# 03_RADIO.net
KiCad netlist of a schematic drawn in Altium Designer
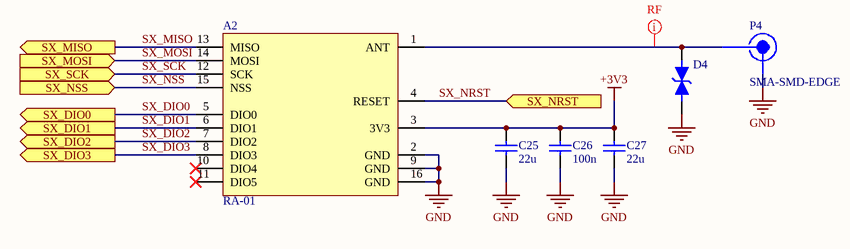
[diagram p0: 03_RADIO.SchDoc]

(export (version "E")
  (design (tool "Eeschema 10.0.6"))
  (components
    (comp (ref "A2")
      (value "RA-01")
      (footprint "RA-01")
      (description "Wireless Modules SX1278")
      (fields (field (name "MANUFACTURER") "Ai-Thinker"))
      (libsource (lib "alfasat_lib") (part "RA-01"))
    )
    (comp (ref "C25")
      (value "22u")
      (footprint "C0805_IPC_HD")
      (description "CAP CER 22UF 16V X5R 0805")
      (fields
        (field (name "MANUFACTURER") "Samsung Electro-Mechanics")
        (field (name "MANUFACTURER PART NUMBER") "CL21A226MOCLRNC")
      )
      (libsource (lib "alfasat_lib") (part "CL21A226MOCLRNC"))
    )
    (comp (ref "C26")
      (value "100n")
      (footprint "C0603_IPC_MD")
      (description "CAP CER 0.1UF 16V X7R 0603")
      (fields
        (field (name "MANUFACTURER") "Samsung Electro-Mechanics")
        (field (name "MANUFACTURER PART NUMBER") "CL10B104KO8NNNC")
      )
      (libsource (lib "alfasat_lib") (part "CL10B104KO8NNNC"))
    )
    (comp (ref "C27")
      (value "22u")
      (footprint "C0805_IPC_HD")
      (description "CAP CER 22UF 16V X5R 0805")
      (fields
        (field (name "MANUFACTURER") "Samsung Electro-Mechanics")
        (field (name "MANUFACTURER PART NUMBER") "CL21A226MOCLRNC")
      )
      (libsource (lib "alfasat_lib") (part "CL21A226MOCLRNC"))
    )
    (comp (ref "D4")
      (value "LXES15AAA1-153")
      (footprint "C0402_IPC_MD")
      (description "TVS DIODE 4V 0402")
      (fields (field (name "MANUFACTURER") "Murata Electronics North America"))
      (libsource (lib "alfasat_lib") (part "LXES15AAA1-153"))
    )
    (comp (ref "P4")
      (value "SMA-SMD-EDGE")
      (footprint "SMA-SMD-EDGE")
      (description "SMA SMD EDGE CONNECTER")
      (fields (field (name "MANUFACTURER") "China"))
      (libsource (lib "alfasat_lib") (part "SMA-SMD-EDGE"))
    )
  )
  (nets
    (net (code "1") (name "+3V3") (class "Default")
      (node (ref "A2") (pin "3") (pinfunction "3V3_3") (pintype "passive"))
      (node (ref "C25") (pin "1") (pinfunction "1_1") (pintype "passive"))
      (node (ref "C26") (pin "1") (pinfunction "1_1") (pintype "passive"))
      (node (ref "C27") (pin "1") (pinfunction "1_1") (pintype "passive"))
    )
    (net (code "2") (name "/SX_DIO0") (class "Default")
      (node (ref "A2") (pin "5") (pinfunction "DIO0_5") (pintype "passive"))
    )
    (net (code "3") (name "/SX_DIO1") (class "Default")
      (node (ref "A2") (pin "6") (pinfunction "DIO1_6") (pintype "passive"))
    )
    (net (code "4") (name "/SX_DIO2") (class "Default")
      (node (ref "A2") (pin "7") (pinfunction "DIO2_7") (pintype "passive"))
    )
    (net (code "5") (name "/SX_DIO3") (class "Default")
      (node (ref "A2") (pin "8") (pinfunction "DIO3_8") (pintype "passive"))
    )
    (net (code "6") (name "/SX_MISO") (class "Default")
      (node (ref "A2") (pin "13") (pinfunction "MISO_13") (pintype "passive"))
    )
    (net (code "7") (name "/SX_MOSI") (class "Default")
      (node (ref "A2") (pin "14") (pinfunction "MOSI_14") (pintype "passive"))
    )
    (net (code "8") (name "/SX_NRST") (class "Default")
      (node (ref "A2") (pin "4") (pinfunction "RESET_4") (pintype "passive"))
    )
    (net (code "9") (name "/SX_NSS") (class "Default")
      (node (ref "A2") (pin "15") (pinfunction "NSS_15") (pintype "passive"))
    )
    (net (code "10") (name "/SX_SCK") (class "Default")
      (node (ref "A2") (pin "12") (pinfunction "SCK_12") (pintype "passive"))
    )
    (net (code "11") (name "GND") (class "Default")
      (node (ref "A2") (pin "16") (pinfunction "GND_16") (pintype "passive"))
      (node (ref "A2") (pin "2") (pinfunction "GND_2") (pintype "passive"))
      (node (ref "A2") (pin "9") (pinfunction "GND_9") (pintype "passive"))
      (node (ref "C25") (pin "2") (pinfunction "2_2") (pintype "passive"))
      (node (ref "C26") (pin "2") (pinfunction "2_2") (pintype "passive"))
      (node (ref "C27") (pin "2") (pinfunction "2_2") (pintype "passive"))
      (node (ref "D4") (pin "1") (pinfunction "1_1") (pintype "passive"))
      (node (ref "P4") (pin "1") (pinfunction "1_1") (pintype "passive"))
    )
    (net (code "12") (name "Net-(A2-ANT)") (class "Default")
      (node (ref "A2") (pin "1") (pinfunction "ANT_1") (pintype "passive"))
      (node (ref "D4") (pin "2") (pinfunction "2_2") (pintype "passive"))
      (node (ref "P4") (pin "2") (pinfunction "2_2") (pintype "passive"))
    )
    (net (code "13") (name "unconnected-(A2-DIO4-Pad10)") (class "Default")
      (node (ref "A2") (pin "10") (pinfunction "DIO4_10") (pintype "passive+no_connect"))
    )
    (net (code "14") (name "unconnected-(A2-DIO5-Pad11)") (class "Default")
      (node (ref "A2") (pin "11") (pinfunction "DIO5_11") (pintype "passive+no_connect"))
    )
  )
)
